# analog.net
KiCad netlist of a schematic drawn in EAGLE
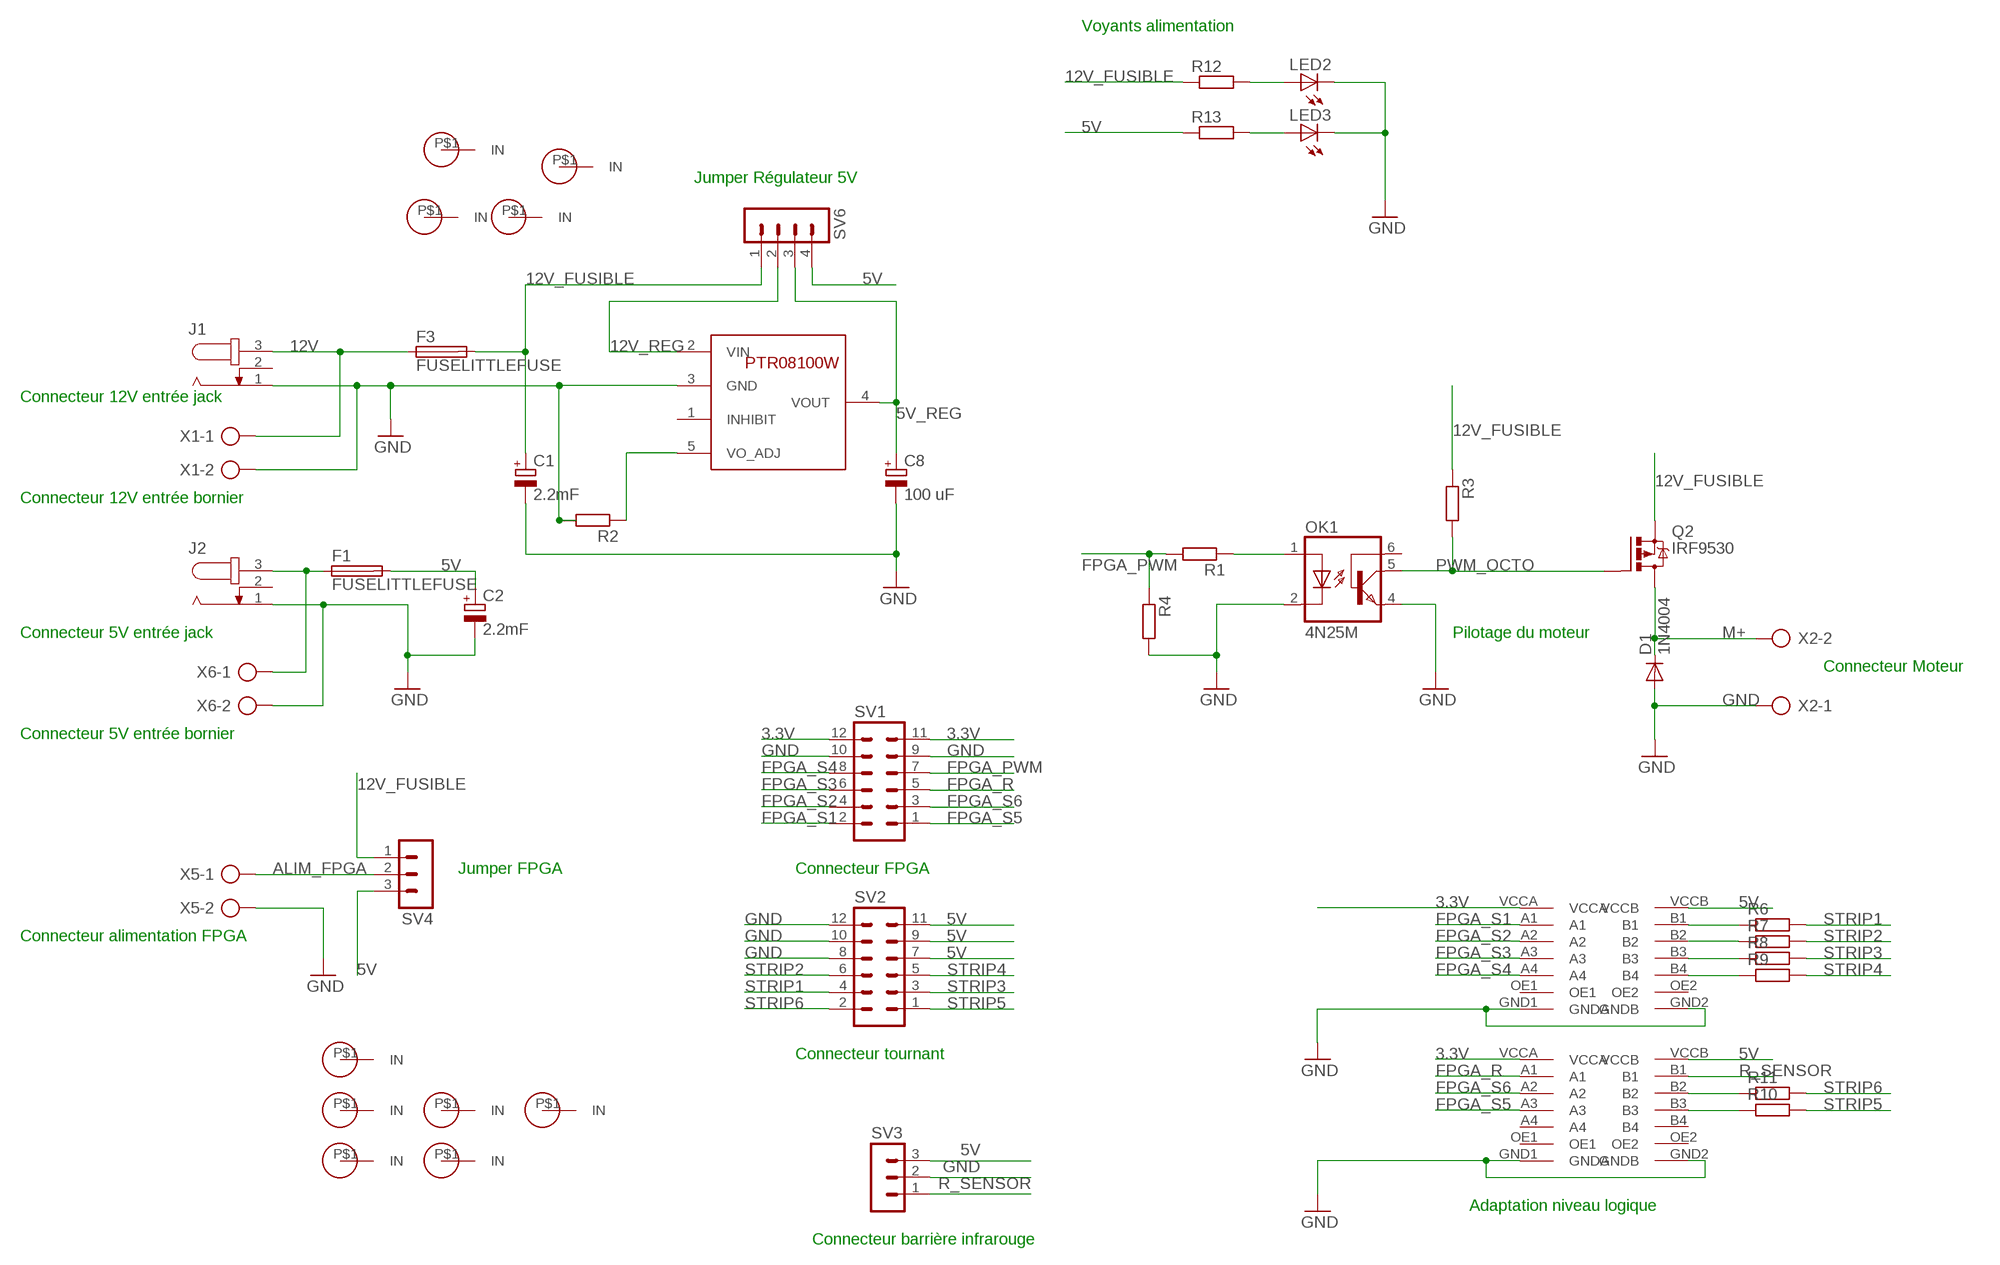
[diagram p0: schematic, sheet 1]

(export (version "E")
  (design (tool "Eeschema 10.0.6"))
  (components
    (comp (ref "C1")
      (value "2.2mF")
      (footprint "eagle-import:E7,5-16")
      (libsource (lib "eagle-import") (part "CPOL-EUE7.5-16"))
    )
    (comp (ref "C2")
      (value "2.2mF")
      (footprint "eagle-import:E7,5-16")
      (libsource (lib "eagle-import") (part "CPOL-EUE7.5-16"))
    )
    (comp (ref "C8")
      (value "100 uF")
      (footprint "eagle-import:E2,5-7")
      (libsource (lib "eagle-import") (part "CPOL-EUE2.5-7"))
    )
    (comp (ref "D1")
      (value "1N4004")
      (footprint "eagle-import:DO41-10")
      (libsource (lib "eagle-import") (part "1N4004"))
    )
    (comp (ref "F1")
      (value "FUSELITTLEFUSE")
      (footprint "eagle-import:LITTLEFUSE")
      (fields (field (name "OC_FARNELL") "unknown") (field (name "OC_NEWARK") "unknown"))
      (libsource (lib "eagle-import") (part "FUSELITTLEFUSE"))
    )
    (comp (ref "F3")
      (value "FUSELITTLEFUSE")
      (footprint "eagle-import:LITTLEFUSE")
      (libsource (lib "eagle-import") (part "FUSELITTLEFUSE"))
    )
    (comp (ref "J1")
      (value "JACK-PLUG1")
      (footprint "eagle-import:SPC4078")
      (libsource (lib "eagle-import") (part "JACK-PLUG1"))
    )
    (comp (ref "J2")
      (value "JACK-PLUG1")
      (footprint "eagle-import:SPC4078")
      (fields (field (name "OC_FARNELL") "unknown") (field (name "OC_NEWARK") "unknown"))
      (libsource (lib "eagle-import") (part "JACK-PLUG1"))
    )
    (comp (ref "LED2")
      (value "LED5MM")
      (footprint "eagle-import:LED5MM")
      (libsource (lib "eagle-import") (part "LED5MM"))
    )
    (comp (ref "LED3")
      (value "LED5MM")
      (footprint "eagle-import:LED5MM")
      (libsource (lib "eagle-import") (part "LED5MM"))
    )
    (comp (ref "OK1")
      (value "4N25M")
      (footprint "eagle-import:DIL06")
      (fields
        (field (name "MPN") "4N25-M")
        (field (name "MPN_1") "4N25-M")
        (field (name "OC_FARNELL") "1021349")
        (field (name "OC_NEWARK") "98K9084")
      )
      (libsource (lib "eagle-import") (part "4N?M25"))
    )
    (comp (ref "Q2")
      (value "IRF9530")
      (footprint "eagle-import:TO220BV")
      (libsource (lib "eagle-import") (part "IRF9530"))
    )
    (comp (ref "R1")
      (value "R-EU_0207/10")
      (footprint "eagle-import:0207_10")
      (libsource (lib "eagle-import") (part "R-EU_0207/10"))
    )
    (comp (ref "R2")
      (value "R-EU_0207/10")
      (footprint "eagle-import:0207_10")
      (libsource (lib "eagle-import") (part "R-EU_0207/10"))
    )
    (comp (ref "R3")
      (value "R-EU_0207/10")
      (footprint "eagle-import:0207_10")
      (libsource (lib "eagle-import") (part "R-EU_0207/10"))
    )
    (comp (ref "R4")
      (value "R-EU_0207/10")
      (footprint "eagle-import:0207_10")
      (libsource (lib "eagle-import") (part "R-EU_0207/10"))
    )
    (comp (ref "R6")
      (value "R-EU_0207/10")
      (footprint "eagle-import:0207_10")
      (libsource (lib "eagle-import") (part "R-EU_0207/10"))
    )
    (comp (ref "R7")
      (value "R-EU_0207/10")
      (footprint "eagle-import:0207_10")
      (libsource (lib "eagle-import") (part "R-EU_0207/10"))
    )
    (comp (ref "R8")
      (value "R-EU_0207/10")
      (footprint "eagle-import:0207_10")
      (libsource (lib "eagle-import") (part "R-EU_0207/10"))
    )
    (comp (ref "R9")
      (value "R-EU_0207/10")
      (footprint "eagle-import:0207_10")
      (libsource (lib "eagle-import") (part "R-EU_0207/10"))
    )
    (comp (ref "R10")
      (value "R-EU_0207/10")
      (footprint "eagle-import:0207_10")
      (libsource (lib "eagle-import") (part "R-EU_0207/10"))
    )
    (comp (ref "R11")
      (value "R-EU_0207/10")
      (footprint "eagle-import:0207_10")
      (libsource (lib "eagle-import") (part "R-EU_0207/10"))
    )
    (comp (ref "R12")
      (value "R-EU_0207/10")
      (footprint "eagle-import:0207_10")
      (libsource (lib "eagle-import") (part "R-EU_0207/10"))
    )
    (comp (ref "R13")
      (value "R-EU_0207/10")
      (footprint "eagle-import:0207_10")
      (libsource (lib "eagle-import") (part "R-EU_0207/10"))
    )
    (comp (ref "SV1")
      (value "MA06-2")
      (footprint "eagle-import:MA06-2")
      (libsource (lib "eagle-import") (part "MA06-2"))
    )
    (comp (ref "SV2")
      (value "MA06-2")
      (footprint "eagle-import:MA06-2")
      (fields (field (name "OC_FARNELL") "unknown") (field (name "OC_NEWARK") "unknown"))
      (libsource (lib "eagle-import") (part "MA06-2"))
    )
    (comp (ref "SV3")
      (value "MA03-1")
      (footprint "eagle-import:MA03-1")
      (libsource (lib "eagle-import") (part "MA03-1"))
    )
    (comp (ref "SV4")
      (value "MA03-1")
      (footprint "eagle-import:MA03-1")
      (libsource (lib "eagle-import") (part "MA03-1"))
    )
    (comp (ref "SV6")
      (value "MA04-1")
      (footprint "eagle-import:MA04-1")
      (libsource (lib "eagle-import") (part "MA04-1"))
    )
    (comp (ref "U$1")
      (value "TXB0104")
      (footprint "eagle-import:TXB0104")
      (libsource (lib "eagle-import") (part "TXB0104"))
    )
    (comp (ref "U$2")
      (value "TXB0104")
      (footprint "eagle-import:TXB0104")
      (libsource (lib "eagle-import") (part "TXB0104"))
    )
    (comp (ref "U$3")
      (value "JUMPER_CONNECTOR")
      (footprint "eagle-import:JUMPER_CONNECTOR")
      (libsource (lib "eagle-import") (part "JUMPER_CONNECTOR"))
    )
    (comp (ref "U$4")
      (value "JUMPER_CONNECTOR")
      (footprint "eagle-import:JUMPER_CONNECTOR")
      (libsource (lib "eagle-import") (part "JUMPER_CONNECTOR"))
    )
    (comp (ref "U$5")
      (value "JUMPER_CONNECTOR")
      (footprint "eagle-import:JUMPER_CONNECTOR")
      (libsource (lib "eagle-import") (part "JUMPER_CONNECTOR"))
    )
    (comp (ref "U$6")
      (value "JUMPER_CONNECTOR")
      (footprint "eagle-import:JUMPER_CONNECTOR")
      (libsource (lib "eagle-import") (part "JUMPER_CONNECTOR"))
    )
    (comp (ref "U$7")
      (value "JUMPER_CONNECTOR")
      (footprint "eagle-import:JUMPER_CONNECTOR")
      (libsource (lib "eagle-import") (part "JUMPER_CONNECTOR"))
    )
    (comp (ref "U$8")
      (value "JUMPER_CONNECTOR")
      (footprint "eagle-import:JUMPER_CONNECTOR")
      (libsource (lib "eagle-import") (part "JUMPER_CONNECTOR"))
    )
    (comp (ref "U$9")
      (value "JUMPER_CONNECTOR")
      (footprint "eagle-import:JUMPER_CONNECTOR")
      (libsource (lib "eagle-import") (part "JUMPER_CONNECTOR"))
    )
    (comp (ref "U$10")
      (value "JUMPER_CONNECTOR")
      (footprint "eagle-import:JUMPER_CONNECTOR")
      (libsource (lib "eagle-import") (part "JUMPER_CONNECTOR"))
    )
    (comp (ref "U$11")
      (value "JUMPER_CONNECTOR")
      (footprint "eagle-import:JUMPER_CONNECTOR")
      (libsource (lib "eagle-import") (part "JUMPER_CONNECTOR"))
    )
    (comp (ref "U$12")
      (value "JUMPER_CONNECTOR")
      (footprint "eagle-import:JUMPER_CONNECTOR")
      (libsource (lib "eagle-import") (part "JUMPER_CONNECTOR"))
    )
    (comp (ref "U2")
      (value "PTR08100W")
      (footprint "eagle-import:PTR08100W")
      (libsource (lib "eagle-import") (part "PTR08100W"))
    )
    (comp (ref "X1")
      (value "AK500/2")
      (footprint "eagle-import:AK500_2")
      (libsource (lib "eagle-import") (part "AK500/2"))
    )
    (comp (ref "X2")
      (value "AK500/2")
      (footprint "eagle-import:AK500_2")
      (libsource (lib "eagle-import") (part "AK500/2"))
    )
    (comp (ref "X5")
      (value "AK500/2")
      (footprint "eagle-import:AK500_2")
      (fields (field (name "OC_FARNELL") "unknown") (field (name "OC_NEWARK") "unknown"))
      (libsource (lib "eagle-import") (part "AK500/2"))
    )
    (comp (ref "X6")
      (value "AK500/2")
      (footprint "eagle-import:AK500_2")
      (fields (field (name "OC_FARNELL") "unknown") (field (name "OC_NEWARK") "unknown"))
      (libsource (lib "eagle-import") (part "AK500/2"))
    )
  )
  (nets
    (net (code "1") (name "/3.3V") (class "Default")
      (node (ref "SV1") (pin "11") (pinfunction "11_11") (pintype "passive"))
      (node (ref "SV1") (pin "12") (pinfunction "12_12") (pintype "passive"))
      (node (ref "U$1") (pin "VCCA") (pinfunction "VCCA_VCCA") (pintype "bidirectional"))
      (node (ref "U$2") (pin "VCCA") (pinfunction "VCCA_VCCA") (pintype "bidirectional"))
    )
    (net (code "2") (name "/5V") (class "Default")
      (node (ref "C2") (pin "+") (pinfunction "+_+") (pintype "passive"))
      (node (ref "F1") (pin "2") (pinfunction "2_2") (pintype "passive"))
      (node (ref "R13") (pin "1") (pinfunction "1_1") (pintype "passive"))
      (node (ref "SV2") (pin "11") (pinfunction "11_11") (pintype "passive"))
      (node (ref "SV2") (pin "7") (pinfunction "7_7") (pintype "passive"))
      (node (ref "SV2") (pin "9") (pinfunction "9_9") (pintype "passive"))
      (node (ref "SV3") (pin "3") (pinfunction "3_3") (pintype "passive"))
      (node (ref "SV4") (pin "3") (pinfunction "3_3") (pintype "passive"))
      (node (ref "SV6") (pin "4") (pinfunction "4_4") (pintype "passive"))
      (node (ref "U$1") (pin "VCCB") (pinfunction "VCCB_VCCB") (pintype "bidirectional"))
      (node (ref "U$2") (pin "VCCB") (pinfunction "VCCB_VCCB") (pintype "bidirectional"))
    )
    (net (code "3") (name "/5V_REG") (class "Default")
      (node (ref "C8") (pin "+") (pinfunction "+_+") (pintype "passive"))
      (node (ref "SV6") (pin "3") (pinfunction "3_3") (pintype "passive"))
      (node (ref "U2") (pin "4") (pinfunction "VOUT_4") (pintype "bidirectional"))
    )
    (net (code "4") (name "/12V") (class "Default")
      (node (ref "F3") (pin "1") (pinfunction "1_1") (pintype "passive"))
      (node (ref "J1") (pin "3") (pinfunction "3_3") (pintype "passive"))
      (node (ref "X1") (pin "1") (pinfunction "KL_1") (pintype "passive"))
    )
    (net (code "5") (name "/12V_FUSIBLE") (class "Default")
      (node (ref "C1") (pin "+") (pinfunction "+_+") (pintype "passive"))
      (node (ref "F3") (pin "2") (pinfunction "2_2") (pintype "passive"))
      (node (ref "Q2") (pin "S") (pinfunction "S_S") (pintype "passive"))
      (node (ref "R12") (pin "1") (pinfunction "1_1") (pintype "passive"))
      (node (ref "R3") (pin "1") (pinfunction "1_1") (pintype "passive"))
      (node (ref "SV4") (pin "1") (pinfunction "1_1") (pintype "passive"))
      (node (ref "SV6") (pin "1") (pinfunction "1_1") (pintype "passive"))
    )
    (net (code "6") (name "/12V_REG") (class "Default")
      (node (ref "SV6") (pin "2") (pinfunction "2_2") (pintype "passive"))
      (node (ref "U2") (pin "2") (pinfunction "VIN_2") (pintype "bidirectional"))
    )
    (net (code "7") (name "/ALIM_FPGA") (class "Default")
      (node (ref "SV4") (pin "2") (pinfunction "2_2") (pintype "passive"))
      (node (ref "X5") (pin "1") (pinfunction "KL_1") (pintype "passive"))
    )
    (net (code "8") (name "/FPGA_PWM") (class "Default")
      (node (ref "R1") (pin "2") (pinfunction "2_2") (pintype "passive"))
      (node (ref "R4") (pin "1") (pinfunction "1_1") (pintype "passive"))
      (node (ref "SV1") (pin "7") (pinfunction "7_7") (pintype "passive"))
    )
    (net (code "9") (name "/FPGA_R") (class "Default")
      (node (ref "SV1") (pin "5") (pinfunction "5_5") (pintype "passive"))
      (node (ref "U$2") (pin "A1") (pinfunction "A1_A1") (pintype "bidirectional"))
    )
    (net (code "10") (name "/FPGA_S1") (class "Default")
      (node (ref "SV1") (pin "2") (pinfunction "2_2") (pintype "passive"))
      (node (ref "U$1") (pin "A1") (pinfunction "A1_A1") (pintype "bidirectional"))
    )
    (net (code "11") (name "/FPGA_S2") (class "Default")
      (node (ref "SV1") (pin "4") (pinfunction "4_4") (pintype "passive"))
      (node (ref "U$1") (pin "A2") (pinfunction "A2_A2") (pintype "bidirectional"))
    )
    (net (code "12") (name "/FPGA_S3") (class "Default")
      (node (ref "SV1") (pin "6") (pinfunction "6_6") (pintype "passive"))
      (node (ref "U$1") (pin "A3") (pinfunction "A3_A3") (pintype "bidirectional"))
    )
    (net (code "13") (name "/FPGA_S4") (class "Default")
      (node (ref "SV1") (pin "8") (pinfunction "8_8") (pintype "passive"))
      (node (ref "U$1") (pin "A4") (pinfunction "A4_A4") (pintype "bidirectional"))
    )
    (net (code "14") (name "/FPGA_S5") (class "Default")
      (node (ref "SV1") (pin "1") (pinfunction "1_1") (pintype "passive"))
      (node (ref "U$2") (pin "A3") (pinfunction "A3_A3") (pintype "bidirectional"))
    )
    (net (code "15") (name "/FPGA_S6") (class "Default")
      (node (ref "SV1") (pin "3") (pinfunction "3_3") (pintype "passive"))
      (node (ref "U$2") (pin "A2") (pinfunction "A2_A2") (pintype "bidirectional"))
    )
    (net (code "16") (name "/M+") (class "Default")
      (node (ref "D1") (pin "C") (pinfunction "C_C") (pintype "passive"))
      (node (ref "Q2") (pin "D") (pinfunction "D_D") (pintype "passive"))
      (node (ref "X2") (pin "2") (pinfunction "KL_2") (pintype "passive"))
    )
    (net (code "17") (name "/PWM_OCTO") (class "Default")
      (node (ref "OK1") (pin "5") (pinfunction "COL_5") (pintype "passive"))
      (node (ref "Q2") (pin "G") (pinfunction "G_G") (pintype "passive"))
      (node (ref "R3") (pin "2") (pinfunction "2_2") (pintype "passive"))
    )
    (net (code "18") (name "/R_SENSOR") (class "Default")
      (node (ref "SV3") (pin "1") (pinfunction "1_1") (pintype "passive"))
      (node (ref "U$2") (pin "B1") (pinfunction "B1_B1") (pintype "bidirectional"))
    )
    (net (code "19") (name "/STRIP1") (class "Default")
      (node (ref "R6") (pin "2") (pinfunction "2_2") (pintype "passive"))
      (node (ref "SV2") (pin "4") (pinfunction "4_4") (pintype "passive"))
    )
    (net (code "20") (name "/STRIP2") (class "Default")
      (node (ref "R7") (pin "2") (pinfunction "2_2") (pintype "passive"))
      (node (ref "SV2") (pin "6") (pinfunction "6_6") (pintype "passive"))
    )
    (net (code "21") (name "/STRIP3") (class "Default")
      (node (ref "R8") (pin "2") (pinfunction "2_2") (pintype "passive"))
      (node (ref "SV2") (pin "3") (pinfunction "3_3") (pintype "passive"))
    )
    (net (code "22") (name "/STRIP4") (class "Default")
      (node (ref "R9") (pin "2") (pinfunction "2_2") (pintype "passive"))
      (node (ref "SV2") (pin "5") (pinfunction "5_5") (pintype "passive"))
    )
    (net (code "23") (name "/STRIP5") (class "Default")
      (node (ref "R10") (pin "2") (pinfunction "2_2") (pintype "passive"))
      (node (ref "SV2") (pin "1") (pinfunction "1_1") (pintype "passive"))
    )
    (net (code "24") (name "/STRIP6") (class "Default")
      (node (ref "R11") (pin "2") (pinfunction "2_2") (pintype "passive"))
      (node (ref "SV2") (pin "2") (pinfunction "2_2") (pintype "passive"))
    )
    (net (code "25") (name "GND") (class "Default")
      (node (ref "C1") (pin "-") (pinfunction "-_-") (pintype "passive"))
      (node (ref "C2") (pin "-") (pinfunction "-_-") (pintype "passive"))
      (node (ref "C8") (pin "-") (pinfunction "-_-") (pintype "passive"))
      (node (ref "D1") (pin "A") (pinfunction "A_A") (pintype "passive"))
      (node (ref "J1") (pin "1") (pinfunction "1_1") (pintype "passive"))
      (node (ref "J2") (pin "1") (pinfunction "1_1") (pintype "passive"))
      (node (ref "LED2") (pin "K") (pinfunction "C_K") (pintype "passive"))
      (node (ref "LED3") (pin "K") (pinfunction "C_K") (pintype "passive"))
      (node (ref "OK1") (pin "2") (pinfunction "C_2") (pintype "passive"))
      (node (ref "OK1") (pin "4") (pinfunction "EMI_4") (pintype "passive"))
      (node (ref "R2") (pin "2") (pinfunction "2_2") (pintype "passive"))
      (node (ref "R4") (pin "2") (pinfunction "2_2") (pintype "passive"))
      (node (ref "SV1") (pin "10") (pinfunction "10_10") (pintype "passive"))
      (node (ref "SV1") (pin "9") (pinfunction "9_9") (pintype "passive"))
      (node (ref "SV2") (pin "10") (pinfunction "10_10") (pintype "passive"))
      (node (ref "SV2") (pin "12") (pinfunction "12_12") (pintype "passive"))
      (node (ref "SV2") (pin "8") (pinfunction "8_8") (pintype "passive"))
      (node (ref "SV3") (pin "2") (pinfunction "2_2") (pintype "passive"))
      (node (ref "U$1") (pin "GND1") (pinfunction "GNDA_GND1") (pintype "bidirectional"))
      (node (ref "U$1") (pin "GND2") (pinfunction "GNDB_GND2") (pintype "bidirectional"))
      (node (ref "U$2") (pin "GND1") (pinfunction "GNDA_GND1") (pintype "bidirectional"))
      (node (ref "U$2") (pin "GND2") (pinfunction "GNDB_GND2") (pintype "bidirectional"))
      (node (ref "U2") (pin "3") (pinfunction "GND_3") (pintype "bidirectional"))
      (node (ref "X1") (pin "2") (pinfunction "KL_2") (pintype "passive"))
      (node (ref "X2") (pin "1") (pinfunction "KL_1") (pintype "passive"))
      (node (ref "X5") (pin "2") (pinfunction "KL_2") (pintype "passive"))
      (node (ref "X6") (pin "2") (pinfunction "KL_2") (pintype "passive"))
    )
    (net (code "26") (name "Net-(LED2-PadA)") (class "Default")
      (node (ref "LED2") (pin "A") (pinfunction "A_A") (pintype "passive"))
      (node (ref "R12") (pin "2") (pinfunction "2_2") (pintype "passive"))
    )
    (net (code "27") (name "Net-(LED3-PadA)") (class "Default")
      (node (ref "LED3") (pin "A") (pinfunction "A_A") (pintype "passive"))
      (node (ref "R13") (pin "2") (pinfunction "2_2") (pintype "passive"))
    )
    (net (code "28") (name "Net-(OK1-A)") (class "Default")
      (node (ref "OK1") (pin "1") (pinfunction "A_1") (pintype "passive"))
      (node (ref "R1") (pin "1") (pinfunction "1_1") (pintype "passive"))
    )
    (net (code "29") (name "Net-(R6-Pad1)") (class "Default")
      (node (ref "R6") (pin "1") (pinfunction "1_1") (pintype "passive"))
      (node (ref "U$1") (pin "B1") (pinfunction "B1_B1") (pintype "bidirectional"))
    )
    (net (code "30") (name "Net-(R7-Pad1)") (class "Default")
      (node (ref "R7") (pin "1") (pinfunction "1_1") (pintype "passive"))
      (node (ref "U$1") (pin "B2") (pinfunction "B2_B2") (pintype "bidirectional"))
    )
    (net (code "31") (name "Net-(R8-Pad1)") (class "Default")
      (node (ref "R8") (pin "1") (pinfunction "1_1") (pintype "passive"))
      (node (ref "U$1") (pin "B3") (pinfunction "B3_B3") (pintype "bidirectional"))
    )
    (net (code "32") (name "Net-(R9-Pad1)") (class "Default")
      (node (ref "R9") (pin "1") (pinfunction "1_1") (pintype "passive"))
      (node (ref "U$1") (pin "B4") (pinfunction "B4_B4") (pintype "bidirectional"))
    )
    (net (code "33") (name "Net-(R10-Pad1)") (class "Default")
      (node (ref "R10") (pin "1") (pinfunction "1_1") (pintype "passive"))
      (node (ref "U$2") (pin "B3") (pinfunction "B3_B3") (pintype "bidirectional"))
    )
    (net (code "34") (name "Net-(R11-Pad1)") (class "Default")
      (node (ref "R11") (pin "1") (pinfunction "1_1") (pintype "passive"))
      (node (ref "U$2") (pin "B2") (pinfunction "B2_B2") (pintype "bidirectional"))
    )
    (net (code "35") (name "Net-(U2-VO_ADJ)") (class "Default")
      (node (ref "R2") (pin "1") (pinfunction "1_1") (pintype "passive"))
      (node (ref "U2") (pin "5") (pinfunction "VO_ADJ_5") (pintype "bidirectional"))
    )
    (net (code "36") (name "Net-(X6A-KL)") (class "Default")
      (node (ref "F1") (pin "1") (pinfunction "1_1") (pintype "passive"))
      (node (ref "J2") (pin "3") (pinfunction "3_3") (pintype "passive"))
      (node (ref "X6") (pin "1") (pinfunction "KL_1") (pintype "passive"))
    )
    (net (code "37") (name "unconnected-(J1-Pad2)") (class "Default")
      (node (ref "J1") (pin "2") (pinfunction "2_2") (pintype "passive"))
    )
    (net (code "38") (name "unconnected-(J2-Pad2)") (class "Default")
      (node (ref "J2") (pin "2") (pinfunction "2_2") (pintype "passive"))
    )
    (net (code "39") (name "unconnected-(OK1-BAS-Pad6)") (class "Default")
      (node (ref "OK1") (pin "6") (pinfunction "BAS_6") (pintype "passive"))
    )
    (net (code "40") (name "unconnected-(U$1-PadOE1)") (class "Default")
      (node (ref "U$1") (pin "OE1") (pinfunction "OE1_OE1") (pintype "bidirectional"))
    )
    (net (code "41") (name "unconnected-(U$1-PadOE2)") (class "Default")
      (node (ref "U$1") (pin "OE2") (pinfunction "OE2_OE2") (pintype "bidirectional"))
    )
    (net (code "42") (name "unconnected-(U$2-PadA4)") (class "Default")
      (node (ref "U$2") (pin "A4") (pinfunction "A4_A4") (pintype "bidirectional"))
    )
    (net (code "43") (name "unconnected-(U$2-PadB4)") (class "Default")
      (node (ref "U$2") (pin "B4") (pinfunction "B4_B4") (pintype "bidirectional"))
    )
    (net (code "44") (name "unconnected-(U$2-PadOE1)") (class "Default")
      (node (ref "U$2") (pin "OE1") (pinfunction "OE1_OE1") (pintype "bidirectional"))
    )
    (net (code "45") (name "unconnected-(U$2-PadOE2)") (class "Default")
      (node (ref "U$2") (pin "OE2") (pinfunction "OE2_OE2") (pintype "bidirectional"))
    )
    (net (code "46") (name "unconnected-(U$3-IN-PadP$1)") (class "Default")
      (node (ref "U$3") (pin "P$1") (pinfunction "IN_P$1") (pintype "bidirectional"))
    )
    (net (code "47") (name "unconnected-(U$4-IN-PadP$1)") (class "Default")
      (node (ref "U$4") (pin "P$1") (pinfunction "IN_P$1") (pintype "bidirectional"))
    )
    (net (code "48") (name "unconnected-(U$5-IN-PadP$1)") (class "Default")
      (node (ref "U$5") (pin "P$1") (pinfunction "IN_P$1") (pintype "bidirectional"))
    )
    (net (code "49") (name "unconnected-(U$6-IN-PadP$1)") (class "Default")
      (node (ref "U$6") (pin "P$1") (pinfunction "IN_P$1") (pintype "bidirectional"))
    )
    (net (code "50") (name "unconnected-(U$7-IN-PadP$1)") (class "Default")
      (node (ref "U$7") (pin "P$1") (pinfunction "IN_P$1") (pintype "bidirectional"))
    )
    (net (code "51") (name "unconnected-(U$8-IN-PadP$1)") (class "Default")
      (node (ref "U$8") (pin "P$1") (pinfunction "IN_P$1") (pintype "bidirectional"))
    )
    (net (code "52") (name "unconnected-(U$9-IN-PadP$1)") (class "Default")
      (node (ref "U$9") (pin "P$1") (pinfunction "IN_P$1") (pintype "bidirectional"))
    )
    (net (code "53") (name "unconnected-(U$10-IN-PadP$1)") (class "Default")
      (node (ref "U$10") (pin "P$1") (pinfunction "IN_P$1") (pintype "bidirectional"))
    )
    (net (code "54") (name "unconnected-(U$11-IN-PadP$1)") (class "Default")
      (node (ref "U$11") (pin "P$1") (pinfunction "IN_P$1") (pintype "bidirectional"))
    )
    (net (code "55") (name "unconnected-(U$12-IN-PadP$1)") (class "Default")
      (node (ref "U$12") (pin "P$1") (pinfunction "IN_P$1") (pintype "bidirectional"))
    )
    (net (code "56") (name "unconnected-(U2-INHIBIT-Pad1)") (class "Default")
      (node (ref "U2") (pin "1") (pinfunction "INHIBIT_1") (pintype "bidirectional"))
    )
  )
)
